# top.net
KiCad netlist of a schematic drawn in Altium Designer
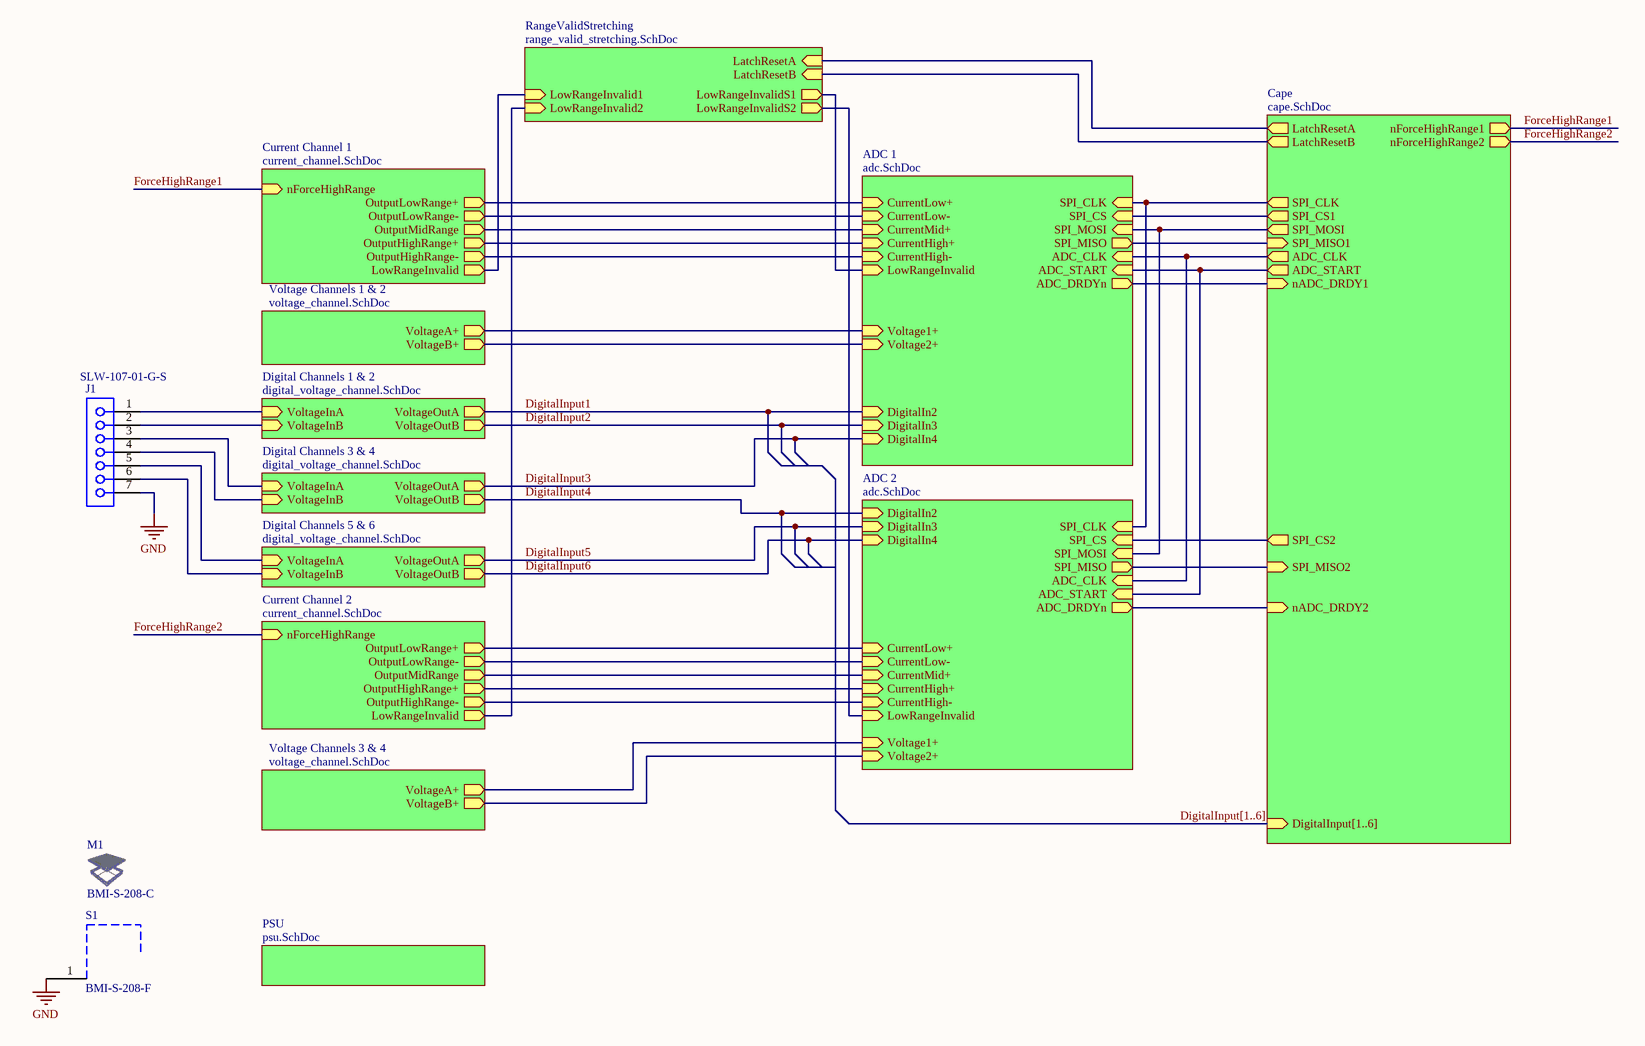
[diagram p0: top.SchDoc]

(export (version "E")
  (design (tool "Eeschema 10.0.6"))
  (components
    (comp (ref "J1")
      (value "SLW-107-01-G-S")
      (footprint "SMTC-SLW-107-01-X-S")
      (fields (field (name "MANUFACTURER") "Samtec"))
      (libsource (lib "Altium Content Vault") (part "SMTC-SLW-107-01-X-S"))
    )
    (comp (ref "M1")
      (value "BMI-S-208-C")
      (description "Board Mount EMI Enclosures RF Absorber CRS Tin SMD")
      (fields (field (name "MANUFACTURER") "Laird"))
      (libsource (lib "ETHZ Vault") (part "BMI-S-206-C"))
    )
    (comp (ref "S1")
      (value "BMI-S-208-F")
      (footprint "BMI-S-208-F")
      (description "EMI Connector Gaskets & Grounding Pads BLS,2PSH,FRM,SnSat .276x1.559x1.559in")
      (fields (field (name "MANUFACTURER") "Laird Technologies EMI"))
      (libsource (lib "ETHZ Vault") (part "EMI Shield"))
    )
  )
  (nets
    (net (code "40") (name "/VoltageInA") (class "Default")
      (node (ref "J1") (pin "3") (pinfunction "3_3") (pintype "passive"))
    )
    (net (code "41") (name "/VoltageInA_1") (class "Default")
      (node (ref "J1") (pin "5") (pinfunction "5_5") (pintype "passive"))
    )
    (net (code "42") (name "/VoltageInA_2") (class "Default")
      (node (ref "J1") (pin "1") (pinfunction "1_1") (pintype "passive"))
    )
    (net (code "43") (name "/VoltageInB") (class "Default")
      (node (ref "J1") (pin "4") (pinfunction "4_4") (pintype "passive"))
    )
    (net (code "44") (name "/VoltageInB_1") (class "Default")
      (node (ref "J1") (pin "6") (pinfunction "6_6") (pintype "passive"))
    )
    (net (code "45") (name "/VoltageInB_2") (class "Default")
      (node (ref "J1") (pin "2") (pinfunction "2_2") (pintype "passive"))
    )
    (net (code "46") (name "GND") (class "Default")
      (node (ref "J1") (pin "7") (pinfunction "7_7") (pintype "passive"))
      (node (ref "S1") (pin "1") (pintype "passive"))
    )
  )
)
